# SCH_Tower_Panda_Hat_2023-01-18.net
KiCad netlist of a schematic drawn in EasyEDA
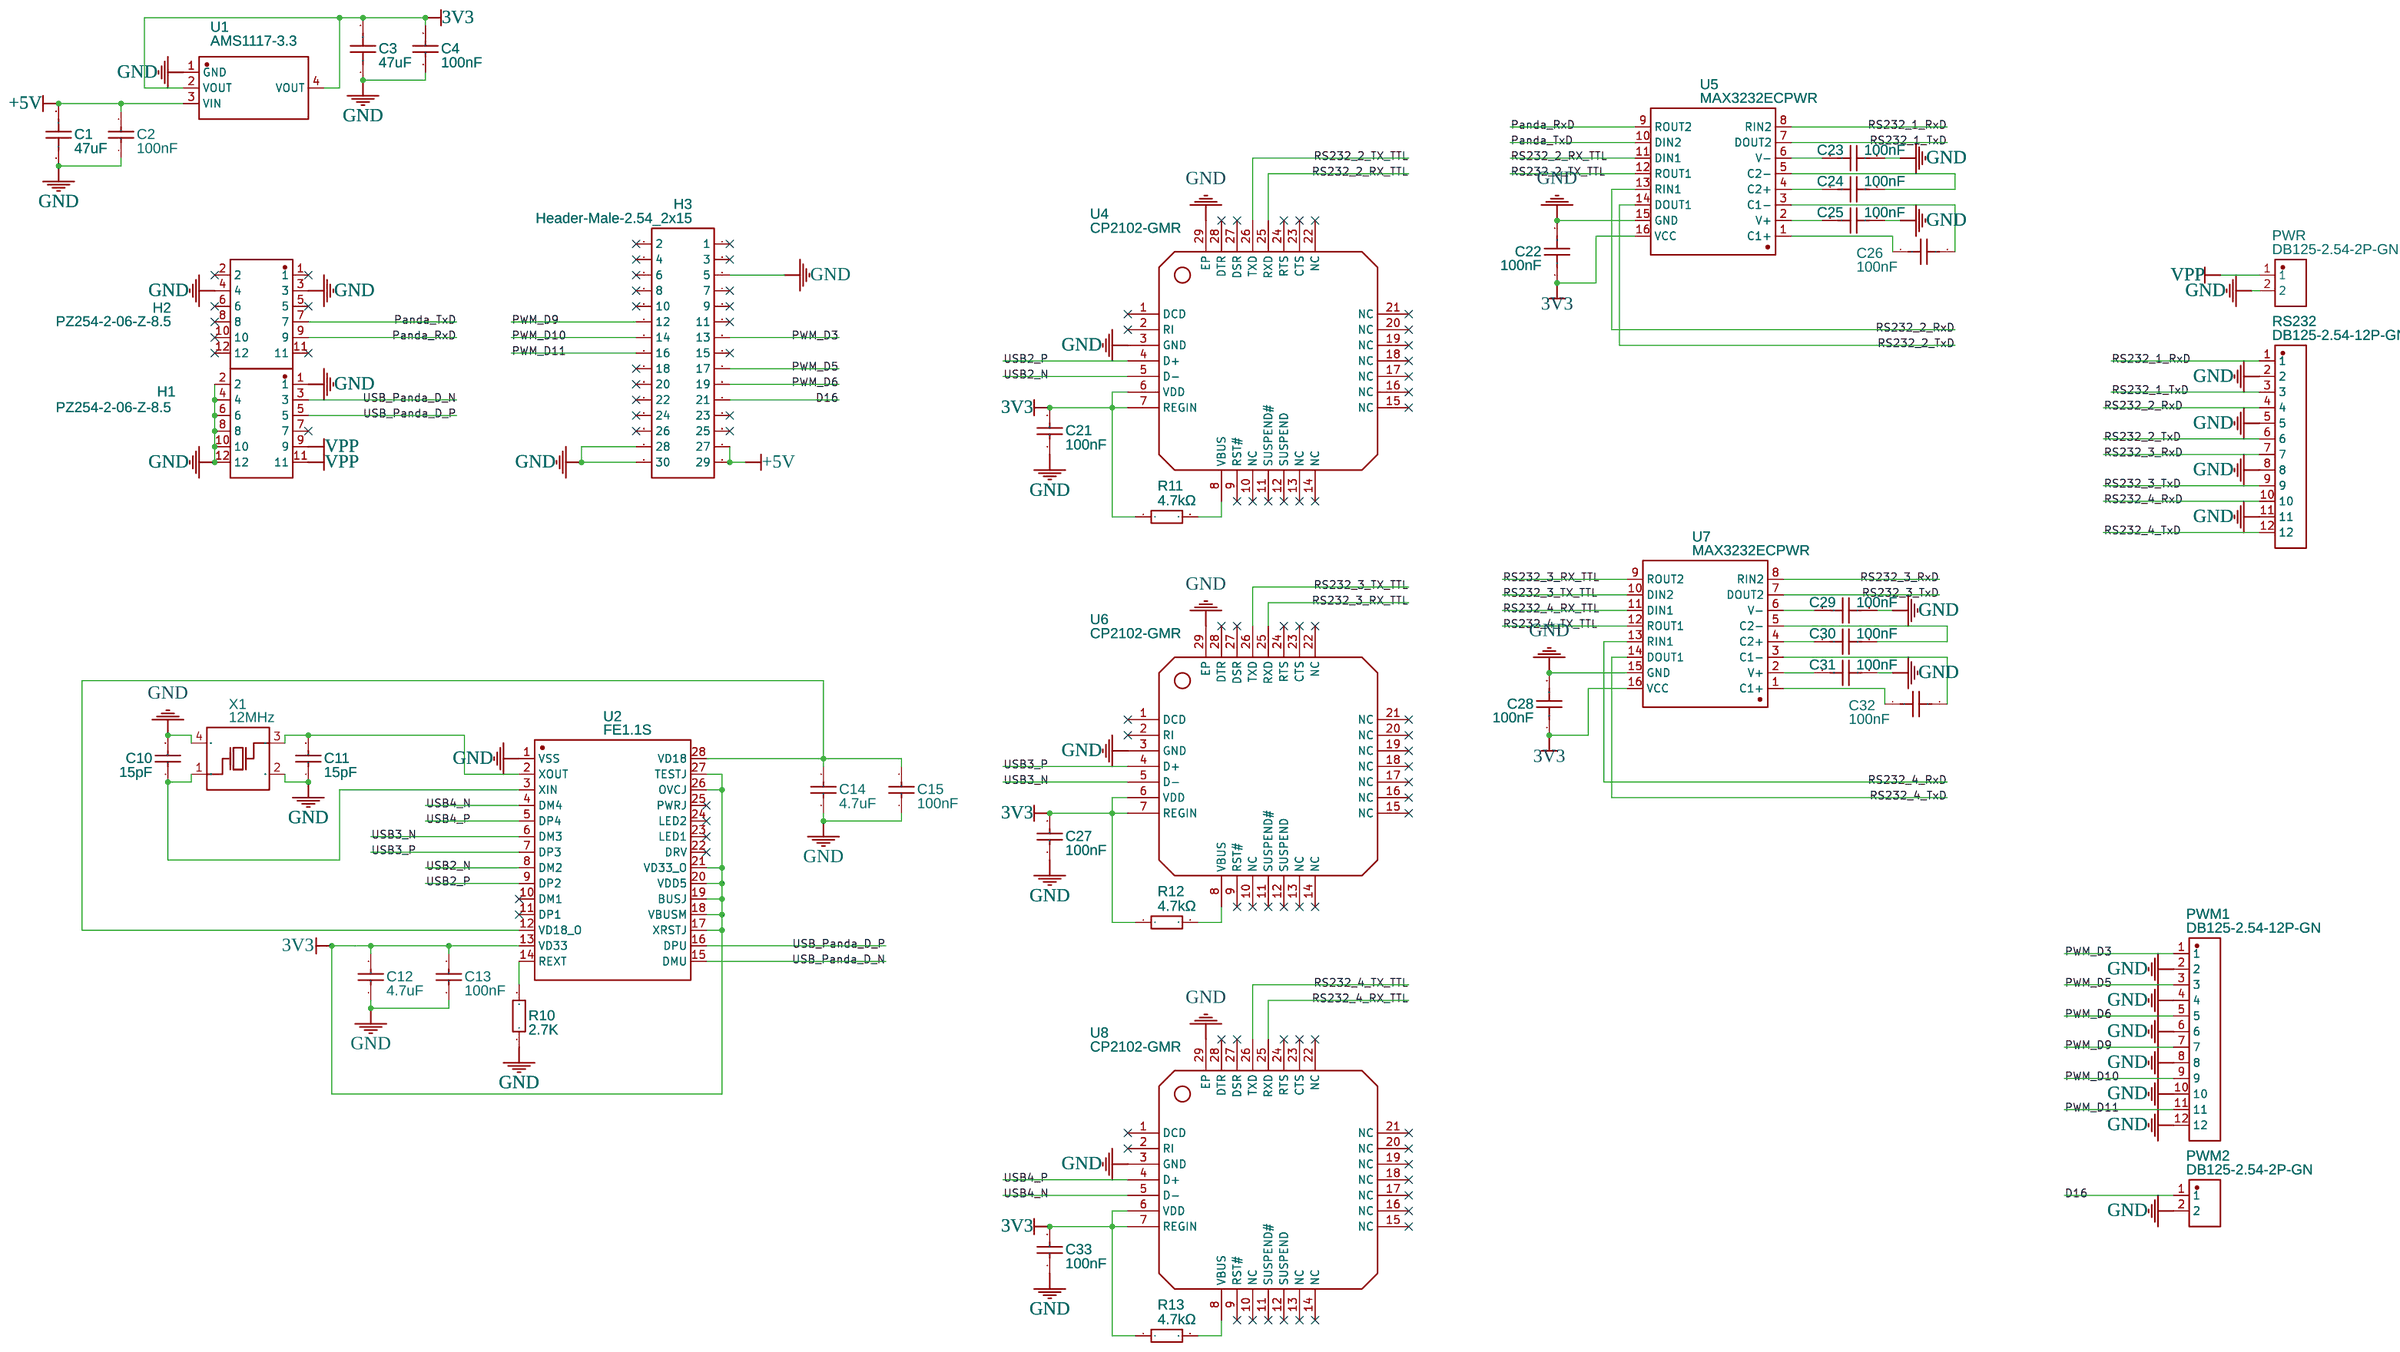
[diagram p0: schematic sheet]

(export (version "E")
  (design (tool "Eeschema 10.0.6"))
  (components
    (comp (ref "C1")
      (value "47uF")
      (fields
        (field (name "BOM_Manufacturer Part") "CL31A476MPHNNNE")
        (field (name "BOM_Supplier Part") "C96123")
      )
      (libsource (lib "") (part "CL31A476MPHNNNE"))
    )
    (comp (ref "C2")
      (value "100nF")
      (fields
        (field (name "BOM_Manufacturer Part") "CL05B104KO5NNNC")
        (field (name "BOM_Supplier Part") "C1525")
      )
      (libsource (lib "") (part "CL05B104KO5NNNC"))
    )
    (comp (ref "C3")
      (value "47uF")
      (fields
        (field (name "BOM_Manufacturer Part") "CL31A476MPHNNNE")
        (field (name "BOM_Supplier Part") "C96123")
      )
      (libsource (lib "") (part "CL31A476MPHNNNE"))
    )
    (comp (ref "C4")
      (value "100nF")
      (fields
        (field (name "BOM_Manufacturer Part") "CL05B104KO5NNNC")
        (field (name "BOM_Supplier Part") "C1525")
      )
      (libsource (lib "") (part "CL05B104KO5NNNC"))
    )
    (comp (ref "C10")
      (value "15pF")
      (fields
        (field (name "BOM_Manufacturer Part") "0402CG150J500NT")
        (field (name "BOM_Supplier Part") "C1548")
      )
      (libsource (lib "") (part "0402CG150J500NT_1"))
    )
    (comp (ref "C11")
      (value "15pF")
      (fields
        (field (name "BOM_Manufacturer Part") "0402CG150J500NT")
        (field (name "BOM_Supplier Part") "C1548")
      )
      (libsource (lib "") (part "0402CG150J500NT"))
    )
    (comp (ref "C12")
      (value "4.7uF")
      (fields
        (field (name "BOM_Manufacturer Part") "CL05A475MP5NRNC")
        (field (name "BOM_Supplier Part") "C23733")
      )
      (libsource (lib "") (part "CL05A475MP5NRNC"))
    )
    (comp (ref "C13")
      (value "100nF")
      (fields
        (field (name "BOM_Manufacturer Part") "CL05B104KO5NNNC")
        (field (name "BOM_Supplier Part") "C1525")
      )
      (libsource (lib "") (part "CL05B104KO5NNNC"))
    )
    (comp (ref "C14")
      (value "4.7uF")
      (fields
        (field (name "BOM_Manufacturer Part") "CL05A475MP5NRNC")
        (field (name "BOM_Supplier Part") "C23733")
      )
      (libsource (lib "") (part "CL05A475MP5NRNC"))
    )
    (comp (ref "C15")
      (value "100nF")
      (fields
        (field (name "BOM_Manufacturer Part") "CL05B104KO5NNNC")
        (field (name "BOM_Supplier Part") "C1525")
      )
      (libsource (lib "") (part "CL05B104KO5NNNC"))
    )
    (comp (ref "C21")
      (value "100nF")
      (fields
        (field (name "BOM_Manufacturer Part") "CL05B104KO5NNNC")
        (field (name "BOM_Supplier Part") "C1525")
      )
      (libsource (lib "") (part "CL05B104KO5NNNC"))
    )
    (comp (ref "C22")
      (value "100nF")
      (fields
        (field (name "BOM_Manufacturer Part") "CL05B104KB54PNC")
        (field (name "BOM_Supplier Part") "C307331")
      )
      (libsource (lib "") (part "CL05B104KB54PNC_1"))
    )
    (comp (ref "C23")
      (value "100nF")
      (fields
        (field (name "BOM_Manufacturer Part") "CL05B104KB54PNC")
        (field (name "BOM_Supplier Part") "C307331")
      )
      (libsource (lib "") (part "CL05B104KB54PNC"))
    )
    (comp (ref "C24")
      (value "100nF")
      (fields
        (field (name "BOM_Manufacturer Part") "CL05B104KB54PNC")
        (field (name "BOM_Supplier Part") "C307331")
      )
      (libsource (lib "") (part "CL05B104KB54PNC"))
    )
    (comp (ref "C25")
      (value "100nF")
      (fields
        (field (name "BOM_Manufacturer Part") "CL05B104KB54PNC")
        (field (name "BOM_Supplier Part") "C307331")
      )
      (libsource (lib "") (part "CL05B104KB54PNC"))
    )
    (comp (ref "C26")
      (value "100nF")
      (fields
        (field (name "BOM_Manufacturer Part") "CL05B104KB54PNC")
        (field (name "BOM_Supplier Part") "C307331")
      )
      (libsource (lib "") (part "CL05B104KB54PNC"))
    )
    (comp (ref "C27")
      (value "100nF")
      (fields
        (field (name "BOM_Manufacturer Part") "CL05B104KO5NNNC")
        (field (name "BOM_Supplier Part") "C1525")
      )
      (libsource (lib "") (part "CL05B104KO5NNNC"))
    )
    (comp (ref "C28")
      (value "100nF")
      (fields
        (field (name "BOM_Manufacturer Part") "CL05B104KB54PNC")
        (field (name "BOM_Supplier Part") "C307331")
      )
      (libsource (lib "") (part "CL05B104KB54PNC_1"))
    )
    (comp (ref "C29")
      (value "100nF")
      (fields
        (field (name "BOM_Manufacturer Part") "CL05B104KB54PNC")
        (field (name "BOM_Supplier Part") "C307331")
      )
      (libsource (lib "") (part "CL05B104KB54PNC"))
    )
    (comp (ref "C30")
      (value "100nF")
      (fields
        (field (name "BOM_Manufacturer Part") "CL05B104KB54PNC")
        (field (name "BOM_Supplier Part") "C307331")
      )
      (libsource (lib "") (part "CL05B104KB54PNC"))
    )
    (comp (ref "C31")
      (value "100nF")
      (fields
        (field (name "BOM_Manufacturer Part") "CL05B104KB54PNC")
        (field (name "BOM_Supplier Part") "C307331")
      )
      (libsource (lib "") (part "CL05B104KB54PNC"))
    )
    (comp (ref "C32")
      (value "100nF")
      (fields
        (field (name "BOM_Manufacturer Part") "CL05B104KB54PNC")
        (field (name "BOM_Supplier Part") "C307331")
      )
      (libsource (lib "") (part "CL05B104KB54PNC"))
    )
    (comp (ref "C33")
      (value "100nF")
      (fields
        (field (name "BOM_Manufacturer Part") "CL05B104KO5NNNC")
        (field (name "BOM_Supplier Part") "C1525")
      )
      (libsource (lib "") (part "CL05B104KO5NNNC"))
    )
    (comp (ref "H1")
      (value "PZ254-2-06-Z-8.5")
      (fields (field (name "BOM_Supplier Part") "C2894967"))
      (libsource (lib "") (part "PZ254-2-06-Z-8.5"))
    )
    (comp (ref "H2")
      (value "PZ254-2-06-Z-8.5")
      (fields (field (name "BOM_Supplier Part") "C2894967"))
      (libsource (lib "") (part "PZ254-2-06-Z-8.5"))
    )
    (comp (ref "H3")
      (value "Header-Male-2.54_2x15")
      (fields
        (field (name "BOM_Manufacturer Part") "2.54-2*15P双排针")
        (field (name "BOM_Supplier Part") "C56496")
      )
      (libsource (lib "") (part "Header-Male-2.54_2x15"))
    )
    (comp (ref "PWM1")
      (value "DB125-2.54-12P-GN")
      (fields
        (field (name "BOM_Manufacturer Part") "DB125-2.54-12P-GN-S")
        (field (name "BOM_Supplier Part") "C918129")
      )
      (libsource (lib "") (part "DB125-2.54-12P-GN_1"))
    )
    (comp (ref "PWM2")
      (value "DB125-2.54-2P-GN")
      (fields (field (name "BOM_Supplier Part") "C918120"))
      (libsource (lib "") (part "DB125-2.54-2P-GN_1"))
    )
    (comp (ref "PWR")
      (value "DB125-2.54-2P-GN")
      (fields (field (name "BOM_Supplier Part") "C918120"))
      (libsource (lib "") (part "DB125-2.54-2P-GN"))
    )
    (comp (ref "R10")
      (value "2.7K")
      (fields
        (field (name "BOM_Manufacturer Part") "0603WAF2701T5E")
        (field (name "BOM_Supplier Part") "C13167")
      )
      (libsource (lib "") (part "0603WAF2701T5E"))
    )
    (comp (ref "R11")
      (value "4.7kΩ")
      (fields
        (field (name "BOM_Manufacturer Part") "0402WGF4701TCE")
        (field (name "BOM_Supplier Part") "C25900")
      )
      (libsource (lib "") (part "0402WGF4701TCE"))
    )
    (comp (ref "R12")
      (value "4.7kΩ")
      (fields
        (field (name "BOM_Manufacturer Part") "0402WGF4701TCE")
        (field (name "BOM_Supplier Part") "C25900")
      )
      (libsource (lib "") (part "0402WGF4701TCE"))
    )
    (comp (ref "R13")
      (value "4.7kΩ")
      (fields
        (field (name "BOM_Manufacturer Part") "0402WGF4701TCE")
        (field (name "BOM_Supplier Part") "C25900")
      )
      (libsource (lib "") (part "0402WGF4701TCE"))
    )
    (comp (ref "RS232")
      (value "DB125-2.54-12P-GN")
      (fields
        (field (name "BOM_Manufacturer Part") "DB125-2.54-12P-GN-S")
        (field (name "BOM_Supplier Part") "C918129")
      )
      (libsource (lib "") (part "DB125-2.54-12P-GN"))
    )
    (comp (ref "U1")
      (value "AMS1117-3.3")
      (fields (field (name "BOM_Supplier Part") "C6186"))
      (libsource (lib "") (part "AMS1117-3.3"))
    )
    (comp (ref "U2")
      (value "FE1.1S")
      (fields (field (name "BOM_Supplier Part") "C9359"))
      (libsource (lib "") (part "FE1.1S"))
    )
    (comp (ref "U4")
      (value "CP2102-GMR")
      (fields (field (name "BOM_Supplier Part") "C6568"))
      (libsource (lib "") (part "CP2102-GMR"))
    )
    (comp (ref "U5")
      (value "MAX3232ECPWR")
      (fields (field (name "BOM_Supplier Part") "C11317"))
      (libsource (lib "") (part "MAX3232ECPWR"))
    )
    (comp (ref "U6")
      (value "CP2102-GMR")
      (fields (field (name "BOM_Supplier Part") "C6568"))
      (libsource (lib "") (part "CP2102-GMR"))
    )
    (comp (ref "U7")
      (value "MAX3232ECPWR")
      (fields (field (name "BOM_Supplier Part") "C11317"))
      (libsource (lib "") (part "MAX3232ECPWR"))
    )
    (comp (ref "U8")
      (value "CP2102-GMR")
      (fields (field (name "BOM_Supplier Part") "C6568"))
      (libsource (lib "") (part "CP2102-GMR"))
    )
    (comp (ref "X1")
      (value "12MHz")
      (fields
        (field (name "BOM_Manufacturer Part") "X322512MSB4SI")
        (field (name "BOM_Supplier Part") "C9002")
      )
      (libsource (lib "") (part "X322512MSB4SI"))
    )
  )
  (nets
    (net (code "1") (name "+5V") (class "Default")
      (node (ref "C1") (pin "2") (pinfunction "2_2") (pintype "unspecified"))
      (node (ref "C2") (pin "2") (pinfunction "2_2") (pintype "input"))
      (node (ref "H3") (pin "27") (pinfunction "27_27") (pintype "input"))
      (node (ref "H3") (pin "29") (pinfunction "29_29") (pintype "input"))
      (node (ref "U1") (pin "3") (pinfunction "VIN_3") (pintype "unspecified"))
    )
    (net (code "2") (name "/D16") (class "Default")
      (node (ref "H3") (pin "21") (pinfunction "21_21") (pintype "input"))
      (node (ref "PWM2") (pin "1") (pinfunction "1_1") (pintype "unspecified"))
    )
    (net (code "3") (name "/PWM_D3") (class "Default")
      (node (ref "H3") (pin "13") (pinfunction "13_13") (pintype "input"))
      (node (ref "PWM1") (pin "1") (pinfunction "1_1") (pintype "unspecified"))
    )
    (net (code "4") (name "/PWM_D5") (class "Default")
      (node (ref "H3") (pin "17") (pinfunction "17_17") (pintype "input"))
      (node (ref "PWM1") (pin "3") (pinfunction "3_3") (pintype "unspecified"))
    )
    (net (code "5") (name "/PWM_D6") (class "Default")
      (node (ref "H3") (pin "19") (pinfunction "19_19") (pintype "input"))
      (node (ref "PWM1") (pin "5") (pinfunction "5_5") (pintype "unspecified"))
    )
    (net (code "6") (name "/PWM_D9") (class "Default")
      (node (ref "H3") (pin "12") (pinfunction "12_12") (pintype "input"))
      (node (ref "PWM1") (pin "7") (pinfunction "7_7") (pintype "unspecified"))
    )
    (net (code "7") (name "/PWM_D10") (class "Default")
      (node (ref "H3") (pin "14") (pinfunction "14_14") (pintype "input"))
      (node (ref "PWM1") (pin "9") (pinfunction "9_9") (pintype "unspecified"))
    )
    (net (code "8") (name "/PWM_D11") (class "Default")
      (node (ref "H3") (pin "16") (pinfunction "16_16") (pintype "input"))
      (node (ref "PWM1") (pin "11") (pinfunction "11_11") (pintype "unspecified"))
    )
    (net (code "9") (name "/Panda_RxD") (class "Default")
      (node (ref "H2") (pin "9") (pinfunction "9_9") (pintype "unspecified"))
      (node (ref "U5") (pin "9") (pinfunction "ROUT2_9") (pintype "unspecified"))
    )
    (net (code "10") (name "/Panda_TxD") (class "Default")
      (node (ref "H2") (pin "7") (pinfunction "7_7") (pintype "unspecified"))
      (node (ref "U5") (pin "10") (pinfunction "DIN2_10") (pintype "unspecified"))
    )
    (net (code "11") (name "/RS232_1_RxD") (class "Default")
      (node (ref "RS232") (pin "1") (pinfunction "1_1") (pintype "unspecified"))
      (node (ref "U5") (pin "8") (pinfunction "RIN2_8") (pintype "unspecified"))
    )
    (net (code "12") (name "/RS232_1_TxD") (class "Default")
      (node (ref "RS232") (pin "3") (pinfunction "3_3") (pintype "unspecified"))
      (node (ref "U5") (pin "7") (pinfunction "DOUT2_7") (pintype "unspecified"))
    )
    (net (code "13") (name "/RS232_2_RX_TTL") (class "Default")
      (node (ref "U4") (pin "25") (pinfunction "RXD_25") (pintype "unspecified"))
      (node (ref "U5") (pin "11") (pinfunction "DIN1_11") (pintype "unspecified"))
    )
    (net (code "14") (name "/RS232_2_RxD") (class "Default")
      (node (ref "RS232") (pin "4") (pinfunction "4_4") (pintype "unspecified"))
      (node (ref "U5") (pin "13") (pinfunction "RIN1_13") (pintype "unspecified"))
    )
    (net (code "15") (name "/RS232_2_TX_TTL") (class "Default")
      (node (ref "U4") (pin "26") (pinfunction "TXD_26") (pintype "unspecified"))
      (node (ref "U5") (pin "12") (pinfunction "ROUT1_12") (pintype "unspecified"))
    )
    (net (code "16") (name "/RS232_2_TxD") (class "Default")
      (node (ref "RS232") (pin "6") (pinfunction "6_6") (pintype "unspecified"))
      (node (ref "U5") (pin "14") (pinfunction "DOUT1_14") (pintype "unspecified"))
    )
    (net (code "17") (name "/RS232_3_RX_TTL") (class "Default")
      (node (ref "U6") (pin "25") (pinfunction "RXD_25") (pintype "unspecified"))
      (node (ref "U7") (pin "9") (pinfunction "ROUT2_9") (pintype "unspecified"))
    )
    (net (code "18") (name "/RS232_3_RxD") (class "Default")
      (node (ref "RS232") (pin "7") (pinfunction "7_7") (pintype "unspecified"))
      (node (ref "U7") (pin "8") (pinfunction "RIN2_8") (pintype "unspecified"))
    )
    (net (code "19") (name "/RS232_3_TX_TTL") (class "Default")
      (node (ref "U6") (pin "26") (pinfunction "TXD_26") (pintype "unspecified"))
      (node (ref "U7") (pin "10") (pinfunction "DIN2_10") (pintype "unspecified"))
    )
    (net (code "20") (name "/RS232_3_TxD") (class "Default")
      (node (ref "RS232") (pin "9") (pinfunction "9_9") (pintype "unspecified"))
      (node (ref "U7") (pin "7") (pinfunction "DOUT2_7") (pintype "unspecified"))
    )
    (net (code "21") (name "/RS232_4_RX_TTL") (class "Default")
      (node (ref "U7") (pin "11") (pinfunction "DIN1_11") (pintype "unspecified"))
      (node (ref "U8") (pin "25") (pinfunction "RXD_25") (pintype "unspecified"))
    )
    (net (code "22") (name "/RS232_4_RxD") (class "Default")
      (node (ref "RS232") (pin "10") (pinfunction "10_10") (pintype "unspecified"))
      (node (ref "U7") (pin "13") (pinfunction "RIN1_13") (pintype "unspecified"))
    )
    (net (code "23") (name "/RS232_4_TX_TTL") (class "Default")
      (node (ref "U7") (pin "12") (pinfunction "ROUT1_12") (pintype "unspecified"))
      (node (ref "U8") (pin "26") (pinfunction "TXD_26") (pintype "unspecified"))
    )
    (net (code "24") (name "/RS232_4_TxD") (class "Default")
      (node (ref "RS232") (pin "12") (pinfunction "12_12") (pintype "unspecified"))
      (node (ref "U7") (pin "14") (pinfunction "DOUT1_14") (pintype "unspecified"))
    )
    (net (code "25") (name "/USB2_N") (class "Default")
      (node (ref "U2") (pin "8") (pinfunction "DM2_8") (pintype "unspecified"))
      (node (ref "U4") (pin "5") (pinfunction "D-_5") (pintype "unspecified"))
    )
    (net (code "26") (name "/USB2_P") (class "Default")
      (node (ref "U2") (pin "9") (pinfunction "DP2_9") (pintype "unspecified"))
      (node (ref "U4") (pin "4") (pinfunction "D+_4") (pintype "unspecified"))
    )
    (net (code "27") (name "/USB3_N") (class "Default")
      (node (ref "U2") (pin "6") (pinfunction "DM3_6") (pintype "unspecified"))
      (node (ref "U6") (pin "5") (pinfunction "D-_5") (pintype "unspecified"))
    )
    (net (code "28") (name "/USB3_P") (class "Default")
      (node (ref "U2") (pin "7") (pinfunction "DP3_7") (pintype "unspecified"))
      (node (ref "U6") (pin "4") (pinfunction "D+_4") (pintype "unspecified"))
    )
    (net (code "29") (name "/USB4_N") (class "Default")
      (node (ref "U2") (pin "4") (pinfunction "DM4_4") (pintype "unspecified"))
      (node (ref "U8") (pin "5") (pinfunction "D-_5") (pintype "unspecified"))
    )
    (net (code "30") (name "/USB4_P") (class "Default")
      (node (ref "U2") (pin "5") (pinfunction "DP4_5") (pintype "unspecified"))
      (node (ref "U8") (pin "4") (pinfunction "D+_4") (pintype "unspecified"))
    )
    (net (code "31") (name "/USB_Panda_D_N") (class "Default")
      (node (ref "H1") (pin "3") (pinfunction "3_3") (pintype "unspecified"))
      (node (ref "U2") (pin "15") (pinfunction "DMU_15") (pintype "unspecified"))
    )
    (net (code "32") (name "/USB_Panda_D_P") (class "Default")
      (node (ref "H1") (pin "5") (pinfunction "5_5") (pintype "unspecified"))
      (node (ref "U2") (pin "16") (pinfunction "DPU_16") (pintype "unspecified"))
    )
    (net (code "33") (name "3V3") (class "Default")
      (node (ref "C12") (pin "2") (pinfunction "2_2") (pintype "input"))
      (node (ref "C13") (pin "2") (pinfunction "2_2") (pintype "input"))
      (node (ref "C21") (pin "2") (pinfunction "2_2") (pintype "input"))
      (node (ref "C22") (pin "1") (pinfunction "1_1") (pintype "unspecified"))
      (node (ref "C27") (pin "2") (pinfunction "2_2") (pintype "input"))
      (node (ref "C28") (pin "1") (pinfunction "1_1") (pintype "unspecified"))
      (node (ref "C3") (pin "2") (pinfunction "2_2") (pintype "unspecified"))
      (node (ref "C33") (pin "2") (pinfunction "2_2") (pintype "input"))
      (node (ref "C4") (pin "2") (pinfunction "2_2") (pintype "input"))
      (node (ref "R11") (pin "1") (pinfunction "1_1") (pintype "input"))
      (node (ref "R12") (pin "1") (pinfunction "1_1") (pintype "input"))
      (node (ref "R13") (pin "1") (pinfunction "1_1") (pintype "input"))
      (node (ref "U1") (pin "2") (pinfunction "VOUT_2") (pintype "unspecified"))
      (node (ref "U1") (pin "4") (pinfunction "VOUT_4") (pintype "unspecified"))
      (node (ref "U2") (pin "13") (pinfunction "VD33_13") (pintype "unspecified"))
      (node (ref "U2") (pin "17") (pinfunction "XRSTJ_17") (pintype "unspecified"))
      (node (ref "U2") (pin "18") (pinfunction "VBUSM_18") (pintype "unspecified"))
      (node (ref "U2") (pin "19") (pinfunction "BUSJ_19") (pintype "unspecified"))
      (node (ref "U2") (pin "20") (pinfunction "VDD5_20") (pintype "unspecified"))
      (node (ref "U2") (pin "21") (pinfunction "VD33_O_21") (pintype "unspecified"))
      (node (ref "U2") (pin "26") (pinfunction "OVCJ_26") (pintype "unspecified"))
      (node (ref "U2") (pin "27") (pinfunction "TESTJ_27") (pintype "unspecified"))
      (node (ref "U4") (pin "6") (pinfunction "VDD_6") (pintype "unspecified"))
      (node (ref "U4") (pin "7") (pinfunction "REGIN_7") (pintype "unspecified"))
      (node (ref "U5") (pin "16") (pinfunction "VCC_16") (pintype "unspecified"))
      (node (ref "U6") (pin "6") (pinfunction "VDD_6") (pintype "unspecified"))
      (node (ref "U6") (pin "7") (pinfunction "REGIN_7") (pintype "unspecified"))
      (node (ref "U7") (pin "16") (pinfunction "VCC_16") (pintype "unspecified"))
      (node (ref "U8") (pin "6") (pinfunction "VDD_6") (pintype "unspecified"))
      (node (ref "U8") (pin "7") (pinfunction "REGIN_7") (pintype "unspecified"))
    )
    (net (code "34") (name "GND") (class "Default")
      (node (ref "C1") (pin "1") (pinfunction "1_1") (pintype "unspecified"))
      (node (ref "C10") (pin "2") (pinfunction "2_2") (pintype "input"))
      (node (ref "C11") (pin "1") (pinfunction "1_1") (pintype "input"))
      (node (ref "C12") (pin "1") (pinfunction "1_1") (pintype "input"))
      (node (ref "C13") (pin "1") (pinfunction "1_1") (pintype "input"))
      (node (ref "C14") (pin "1") (pinfunction "1_1") (pintype "input"))
      (node (ref "C15") (pin "1") (pinfunction "1_1") (pintype "input"))
      (node (ref "C2") (pin "1") (pinfunction "1_1") (pintype "input"))
      (node (ref "C21") (pin "1") (pinfunction "1_1") (pintype "input"))
      (node (ref "C22") (pin "2") (pinfunction "2_2") (pintype "unspecified"))
      (node (ref "C23") (pin "2") (pinfunction "2_2") (pintype "unspecified"))
      (node (ref "C25") (pin "2") (pinfunction "2_2") (pintype "unspecified"))
      (node (ref "C27") (pin "1") (pinfunction "1_1") (pintype "input"))
      (node (ref "C28") (pin "2") (pinfunction "2_2") (pintype "unspecified"))
      (node (ref "C29") (pin "2") (pinfunction "2_2") (pintype "unspecified"))
      (node (ref "C3") (pin "1") (pinfunction "1_1") (pintype "unspecified"))
      (node (ref "C31") (pin "2") (pinfunction "2_2") (pintype "unspecified"))
      (node (ref "C33") (pin "1") (pinfunction "1_1") (pintype "input"))
      (node (ref "C4") (pin "1") (pinfunction "1_1") (pintype "input"))
      (node (ref "H1") (pin "1") (pinfunction "1_1") (pintype "unspecified"))
      (node (ref "H1") (pin "10") (pinfunction "10_10") (pintype "unspecified"))
      (node (ref "H1") (pin "12") (pinfunction "12_12") (pintype "unspecified"))
      (node (ref "H1") (pin "2") (pinfunction "2_2") (pintype "unspecified"))
      (node (ref "H1") (pin "4") (pinfunction "4_4") (pintype "unspecified"))
      (node (ref "H1") (pin "6") (pinfunction "6_6") (pintype "unspecified"))
      (node (ref "H1") (pin "8") (pinfunction "8_8") (pintype "unspecified"))
      (node (ref "H2") (pin "3") (pinfunction "3_3") (pintype "unspecified"))
      (node (ref "H2") (pin "4") (pinfunction "4_4") (pintype "unspecified"))
      (node (ref "H3") (pin "28") (pinfunction "28_28") (pintype "input"))
      (node (ref "H3") (pin "30") (pinfunction "30_30") (pintype "input"))
      (node (ref "H3") (pin "5") (pinfunction "5_5") (pintype "input"))
      (node (ref "PWM1") (pin "10") (pinfunction "10_10") (pintype "unspecified"))
      (node (ref "PWM1") (pin "12") (pinfunction "12_12") (pintype "unspecified"))
      (node (ref "PWM1") (pin "2") (pinfunction "2_2") (pintype "unspecified"))
      (node (ref "PWM1") (pin "4") (pinfunction "4_4") (pintype "unspecified"))
      (node (ref "PWM1") (pin "6") (pinfunction "6_6") (pintype "unspecified"))
      (node (ref "PWM1") (pin "8") (pinfunction "8_8") (pintype "unspecified"))
      (node (ref "PWM2") (pin "2") (pinfunction "2_2") (pintype "unspecified"))
      (node (ref "PWR") (pin "2") (pinfunction "2_2") (pintype "unspecified"))
      (node (ref "R10") (pin "1") (pinfunction "1_1") (pintype "input"))
      (node (ref "RS232") (pin "11") (pinfunction "11_11") (pintype "unspecified"))
      (node (ref "RS232") (pin "2") (pinfunction "2_2") (pintype "unspecified"))
      (node (ref "RS232") (pin "5") (pinfunction "5_5") (pintype "unspecified"))
      (node (ref "RS232") (pin "8") (pinfunction "8_8") (pintype "unspecified"))
      (node (ref "U1") (pin "1") (pinfunction "GND_1") (pintype "unspecified"))
      (node (ref "U2") (pin "1") (pinfunction "VSS_1") (pintype "unspecified"))
      (node (ref "U4") (pin "29") (pinfunction "EP_29") (pintype "unspecified"))
      (node (ref "U4") (pin "3") (pinfunction "GND_3") (pintype "unspecified"))
      (node (ref "U5") (pin "15") (pinfunction "GND_15") (pintype "unspecified"))
      (node (ref "U6") (pin "29") (pinfunction "EP_29") (pintype "unspecified"))
      (node (ref "U6") (pin "3") (pinfunction "GND_3") (pintype "unspecified"))
      (node (ref "U7") (pin "15") (pinfunction "GND_15") (pintype "unspecified"))
      (node (ref "U8") (pin "29") (pinfunction "EP_29") (pintype "unspecified"))
      (node (ref "U8") (pin "3") (pinfunction "GND_3") (pintype "unspecified"))
      (node (ref "X1") (pin "2") (pinfunction "GND_2") (pintype "unspecified"))
      (node (ref "X1") (pin "4") (pinfunction "GND_4") (pintype "unspecified"))
    )
    (net (code "35") (name "Net-(U2-REXT)") (class "Default")
      (node (ref "R10") (pin "2") (pinfunction "2_2") (pintype "input"))
      (node (ref "U2") (pin "14") (pinfunction "REXT_14") (pintype "unspecified"))
    )
    (net (code "36") (name "Net-(U2-VD18)") (class "Default")
      (node (ref "C14") (pin "2") (pinfunction "2_2") (pintype "input"))
      (node (ref "C15") (pin "2") (pinfunction "2_2") (pintype "input"))
      (node (ref "U2") (pin "12") (pinfunction "VD18_O_12") (pintype "unspecified"))
      (node (ref "U2") (pin "28") (pinfunction "VD18_28") (pintype "unspecified"))
    )
    (net (code "37") (name "Net-(U2-XIN)") (class "Default")
      (node (ref "C10") (pin "1") (pinfunction "1_1") (pintype "input"))
      (node (ref "U2") (pin "3") (pinfunction "XIN_3") (pintype "unspecified"))
      (node (ref "X1") (pin "1") (pinfunction "OSC1_1") (pintype "unspecified"))
    )
    (net (code "38") (name "Net-(U2-XOUT)") (class "Default")
      (node (ref "C11") (pin "2") (pinfunction "2_2") (pintype "input"))
      (node (ref "U2") (pin "2") (pinfunction "XOUT_2") (pintype "unspecified"))
      (node (ref "X1") (pin "3") (pinfunction "OSC2_3") (pintype "unspecified"))
    )
    (net (code "39") (name "Net-(U4-VBUS)") (class "Default")
      (node (ref "R11") (pin "2") (pinfunction "2_2") (pintype "input"))
      (node (ref "U4") (pin "8") (pinfunction "VBUS_8") (pintype "unspecified"))
    )
    (net (code "40") (name "Net-(U5-C1+)") (class "Default")
      (node (ref "C26") (pin "1") (pinfunction "1_1") (pintype "unspecified"))
      (node (ref "U5") (pin "1") (pinfunction "C1+_1") (pintype "unspecified"))
    )
    (net (code "41") (name "Net-(U5-C1-)") (class "Default")
      (node (ref "C26") (pin "2") (pinfunction "2_2") (pintype "unspecified"))
      (node (ref "U5") (pin "3") (pinfunction "C1-_3") (pintype "unspecified"))
    )
    (net (code "42") (name "Net-(U5-C2+)") (class "Default")
      (node (ref "C24") (pin "1") (pinfunction "1_1") (pintype "unspecified"))
      (node (ref "U5") (pin "4") (pinfunction "C2+_4") (pintype "unspecified"))
    )
    (net (code "43") (name "Net-(U5-C2-)") (class "Default")
      (node (ref "C24") (pin "2") (pinfunction "2_2") (pintype "unspecified"))
      (node (ref "U5") (pin "5") (pinfunction "C2-_5") (pintype "unspecified"))
    )
    (net (code "44") (name "Net-(U5-V+)") (class "Default")
      (node (ref "C25") (pin "1") (pinfunction "1_1") (pintype "unspecified"))
      (node (ref "U5") (pin "2") (pinfunction "V+_2") (pintype "unspecified"))
    )
    (net (code "45") (name "Net-(U5-V-)") (class "Default")
      (node (ref "C23") (pin "1") (pinfunction "1_1") (pintype "unspecified"))
      (node (ref "U5") (pin "6") (pinfunction "V-_6") (pintype "unspecified"))
    )
    (net (code "46") (name "Net-(U6-VBUS)") (class "Default")
      (node (ref "R12") (pin "2") (pinfunction "2_2") (pintype "input"))
      (node (ref "U6") (pin "8") (pinfunction "VBUS_8") (pintype "unspecified"))
    )
    (net (code "47") (name "Net-(U7-C1+)") (class "Default")
      (node (ref "C32") (pin "1") (pinfunction "1_1") (pintype "unspecified"))
      (node (ref "U7") (pin "1") (pinfunction "C1+_1") (pintype "unspecified"))
    )
    (net (code "48") (name "Net-(U7-C1-)") (class "Default")
      (node (ref "C32") (pin "2") (pinfunction "2_2") (pintype "unspecified"))
      (node (ref "U7") (pin "3") (pinfunction "C1-_3") (pintype "unspecified"))
    )
    (net (code "49") (name "Net-(U7-C2+)") (class "Default")
      (node (ref "C30") (pin "1") (pinfunction "1_1") (pintype "unspecified"))
      (node (ref "U7") (pin "4") (pinfunction "C2+_4") (pintype "unspecified"))
    )
    (net (code "50") (name "Net-(U7-C2-)") (class "Default")
      (node (ref "C30") (pin "2") (pinfunction "2_2") (pintype "unspecified"))
      (node (ref "U7") (pin "5") (pinfunction "C2-_5") (pintype "unspecified"))
    )
    (net (code "51") (name "Net-(U7-V+)") (class "Default")
      (node (ref "C31") (pin "1") (pinfunction "1_1") (pintype "unspecified"))
      (node (ref "U7") (pin "2") (pinfunction "V+_2") (pintype "unspecified"))
    )
    (net (code "52") (name "Net-(U7-V-)") (class "Default")
      (node (ref "C29") (pin "1") (pinfunction "1_1") (pintype "unspecified"))
      (node (ref "U7") (pin "6") (pinfunction "V-_6") (pintype "unspecified"))
    )
    (net (code "53") (name "Net-(U8-VBUS)") (class "Default")
      (node (ref "R13") (pin "2") (pinfunction "2_2") (pintype "input"))
      (node (ref "U8") (pin "8") (pinfunction "VBUS_8") (pintype "unspecified"))
    )
    (net (code "54") (name "VPP") (class "Default")
      (node (ref "H1") (pin "11") (pinfunction "11_11") (pintype "unspecified"))
      (node (ref "H1") (pin "9") (pinfunction "9_9") (pintype "unspecified"))
      (node (ref "PWR") (pin "1") (pinfunction "1_1") (pintype "unspecified"))
    )
    (net (code "55") (name "unconnected-(H1-Pad7)") (class "Default")
      (node (ref "H1") (pin "7") (pinfunction "7_7") (pintype "unspecified+no_connect"))
    )
    (net (code "56") (name "unconnected-(H2-Pad1)") (class "Default")
      (node (ref "H2") (pin "1") (pinfunction "1_1") (pintype "unspecified+no_connect"))
    )
    (net (code "57") (name "unconnected-(H2-Pad2)") (class "Default")
      (node (ref "H2") (pin "2") (pinfunction "2_2") (pintype "unspecified+no_connect"))
    )
    (net (code "58") (name "unconnected-(H2-Pad5)") (class "Default")
      (node (ref "H2") (pin "5") (pinfunction "5_5") (pintype "unspecified+no_connect"))
    )
    (net (code "59") (name "unconnected-(H2-Pad6)") (class "Default")
      (node (ref "H2") (pin "6") (pinfunction "6_6") (pintype "unspecified+no_connect"))
    )
    (net (code "60") (name "unconnected-(H2-Pad8)") (class "Default")
      (node (ref "H2") (pin "8") (pinfunction "8_8") (pintype "unspecified+no_connect"))
    )
    (net (code "61") (name "unconnected-(H2-Pad10)") (class "Default")
      (node (ref "H2") (pin "10") (pinfunction "10_10") (pintype "unspecified+no_connect"))
    )
    (net (code "62") (name "unconnected-(H2-Pad11)") (class "Default")
      (node (ref "H2") (pin "11") (pinfunction "11_11") (pintype "unspecified+no_connect"))
    )
    (net (code "63") (name "unconnected-(H2-Pad12)") (class "Default")
      (node (ref "H2") (pin "12") (pinfunction "12_12") (pintype "unspecified+no_connect"))
    )
    (net (code "64") (name "unconnected-(H3-Pad1)") (class "Default")
      (node (ref "H3") (pin "1") (pinfunction "1_1") (pintype "input+no_connect"))
    )
    (net (code "65") (name "unconnected-(H3-Pad2)") (class "Default")
      (node (ref "H3") (pin "2") (pinfunction "2_2") (pintype "input+no_connect"))
    )
    (net (code "66") (name "unconnected-(H3-Pad3)") (class "Default")
      (node (ref "H3") (pin "3") (pinfunction "3_3") (pintype "input+no_connect"))
    )
    (net (code "67") (name "unconnected-(H3-Pad4)") (class "Default")
      (node (ref "H3") (pin "4") (pinfunction "4_4") (pintype "input+no_connect"))
    )
    (net (code "68") (name "unconnected-(H3-Pad6)") (class "Default")
      (node (ref "H3") (pin "6") (pinfunction "6_6") (pintype "input+no_connect"))
    )
    (net (code "69") (name "unconnected-(H3-Pad7)") (class "Default")
      (node (ref "H3") (pin "7") (pinfunction "7_7") (pintype "input+no_connect"))
    )
    (net (code "70") (name "unconnected-(H3-Pad8)") (class "Default")
      (node (ref "H3") (pin "8") (pinfunction "8_8") (pintype "input+no_connect"))
    )
    (net (code "71") (name "unconnected-(H3-Pad9)") (class "Default")
      (node (ref "H3") (pin "9") (pinfunction "9_9") (pintype "input+no_connect"))
    )
    (net (code "72") (name "unconnected-(H3-Pad10)") (class "Default")
      (node (ref "H3") (pin "10") (pinfunction "10_10") (pintype "input+no_connect"))
    )
    (net (code "73") (name "unconnected-(H3-Pad11)") (class "Default")
      (node (ref "H3") (pin "11") (pinfunction "11_11") (pintype "input+no_connect"))
    )
    (net (code "74") (name "unconnected-(H3-Pad15)") (class "Default")
      (node (ref "H3") (pin "15") (pinfunction "15_15") (pintype "input+no_connect"))
    )
    (net (code "75") (name "unconnected-(H3-Pad18)") (class "Default")
      (node (ref "H3") (pin "18") (pinfunction "18_18") (pintype "input+no_connect"))
    )
    (net (code "76") (name "unconnected-(H3-Pad20)") (class "Default")
      (node (ref "H3") (pin "20") (pinfunction "20_20") (pintype "input+no_connect"))
    )
    (net (code "77") (name "unconnected-(H3-Pad22)") (class "Default")
      (node (ref "H3") (pin "22") (pinfunction "22_22") (pintype "input+no_connect"))
    )
    (net (code "78") (name "unconnected-(H3-Pad23)") (class "Default")
      (node (ref "H3") (pin "23") (pinfunction "23_23") (pintype "input+no_connect"))
    )
    (net (code "79") (name "unconnected-(H3-Pad24)") (class "Default")
      (node (ref "H3") (pin "24") (pinfunction "24_24") (pintype "input+no_connect"))
    )
    (net (code "80") (name "unconnected-(H3-Pad25)") (class "Default")
      (node (ref "H3") (pin "25") (pinfunction "25_25") (pintype "input+no_connect"))
    )
    (net (code "81") (name "unconnected-(H3-Pad26)") (class "Default")
      (node (ref "H3") (pin "26") (pinfunction "26_26") (pintype "input+no_connect"))
    )
    (net (code "82") (name "unconnected-(U2-DM1-Pad10)") (class "Default")
      (node (ref "U2") (pin "10") (pinfunction "DM1_10") (pintype "unspecified+no_connect"))
    )
    (net (code "83") (name "unconnected-(U2-DP1-Pad11)") (class "Default")
      (node (ref "U2") (pin "11") (pinfunction "DP1_11") (pintype "unspecified+no_connect"))
    )
    (net (code "84") (name "unconnected-(U2-DRV-Pad22)") (class "Default")
      (node (ref "U2") (pin "22") (pinfunction "DRV_22") (pintype "unspecified+no_connect"))
    )
    (net (code "85") (name "unconnected-(U2-LED1-Pad23)") (class "Default")
      (node (ref "U2") (pin "23") (pinfunction "LED1_23") (pintype "unspecified+no_connect"))
    )
    (net (code "86") (name "unconnected-(U2-LED2-Pad24)") (class "Default")
      (node (ref "U2") (pin "24") (pinfunction "LED2_24") (pintype "unspecified+no_connect"))
    )
    (net (code "87") (name "unconnected-(U2-PWRJ-Pad25)") (class "Default")
      (node (ref "U2") (pin "25") (pinfunction "PWRJ_25") (pintype "unspecified+no_connect"))
    )
    (net (code "88") (name "unconnected-(U4-CTS-Pad23)") (class "Default")
      (node (ref "U4") (pin "23") (pinfunction "CTS_23") (pintype "unspecified+no_connect"))
    )
    (net (code "89") (name "unconnected-(U4-DCD-Pad1)") (class "Default")
      (node (ref "U4") (pin "1") (pinfunction "DCD_1") (pintype "unspecified+no_connect"))
    )
    (net (code "90") (name "unconnected-(U4-DSR-Pad27)") (class "Default")
      (node (ref "U4") (pin "27") (pinfunction "DSR_27") (pintype "unspecified+no_connect"))
    )
    (net (code "91") (name "unconnected-(U4-DTR-Pad28)") (class "Default")
      (node (ref "U4") (pin "28") (pinfunction "DTR_28") (pintype "unspecified+no_connect"))
    )
    (net (code "92") (name "unconnected-(U4-NC-Pad10)") (class "Default")
      (node (ref "U4") (pin "10") (pinfunction "NC_10") (pintype "unspecified+no_connect"))
    )
    (net (code "93") (name "unconnected-(U4-NC-Pad13)") (class "Default")
      (node (ref "U4") (pin "13") (pinfunction "NC_13") (pintype "unspecified+no_connect"))
    )
    (net (code "94") (name "unconnected-(U4-NC-Pad14)") (class "Default")
      (node (ref "U4") (pin "14") (pinfunction "NC_14") (pintype "unspecified+no_connect"))
    )
    (net (code "95") (name "unconnected-(U4-NC-Pad15)") (class "Default")
      (node (ref "U4") (pin "15") (pinfunction "NC_15") (pintype "unspecified+no_connect"))
    )
    (net (code "96") (name "unconnected-(U4-NC-Pad16)") (class "Default")
      (node (ref "U4") (pin "16") (pinfunction "NC_16") (pintype "unspecified+no_connect"))
    )
    (net (code "97") (name "unconnected-(U4-NC-Pad17)") (class "Default")
      (node (ref "U4") (pin "17") (pinfunction "NC_17") (pintype "unspecified+no_connect"))
    )
    (net (code "98") (name "unconnected-(U4-NC-Pad18)") (class "Default")
      (node (ref "U4") (pin "18") (pinfunction "NC_18") (pintype "unspecified+no_connect"))
    )
    (net (code "99") (name "unconnected-(U4-NC-Pad19)") (class "Default")
      (node (ref "U4") (pin "19") (pinfunction "NC_19") (pintype "unspecified+no_connect"))
    )
    (net (code "100") (name "unconnected-(U4-NC-Pad20)") (class "Default")
      (node (ref "U4") (pin "20") (pinfunction "NC_20") (pintype "unspecified+no_connect"))
    )
    (net (code "101") (name "unconnected-(U4-NC-Pad21)") (class "Default")
      (node (ref "U4") (pin "21") (pinfunction "NC_21") (pintype "unspecified+no_connect"))
    )
    (net (code "102") (name "unconnected-(U4-NC-Pad22)") (class "Default")
      (node (ref "U4") (pin "22") (pinfunction "NC_22") (pintype "unspecified+no_connect"))
    )
    (net (code "103") (name "unconnected-(U4-RI-Pad2)") (class "Default")
      (node (ref "U4") (pin "2") (pinfunction "RI_2") (pintype "unspecified+no_connect"))
    )
    (net (code "104") (name "unconnected-(U4-RST#-Pad9)") (class "Default")
      (node (ref "U4") (pin "9") (pinfunction "RST#_9") (pintype "unspecified+no_connect"))
    )
    (net (code "105") (name "unconnected-(U4-RTS-Pad24)") (class "Default")
      (node (ref "U4") (pin "24") (pinfunction "RTS_24") (pintype "unspecified+no_connect"))
    )
    (net (code "106") (name "unconnected-(U4-SUSPEND#-Pad11)") (class "Default")
      (node (ref "U4") (pin "11") (pinfunction "SUSPEND#_11") (pintype "unspecified+no_connect"))
    )
    (net (code "107") (name "unconnected-(U4-SUSPEND-Pad12)") (class "Default")
      (node (ref "U4") (pin "12") (pinfunction "SUSPEND_12") (pintype "unspecified+no_connect"))
    )
    (net (code "108") (name "unconnected-(U6-CTS-Pad23)") (class "Default")
      (node (ref "U6") (pin "23") (pinfunction "CTS_23") (pintype "unspecified+no_connect"))
    )
    (net (code "109") (name "unconnected-(U6-DCD-Pad1)") (class "Default")
      (node (ref "U6") (pin "1") (pinfunction "DCD_1") (pintype "unspecified+no_connect"))
    )
    (net (code "110") (name "unconnected-(U6-DSR-Pad27)") (class "Default")
      (node (ref "U6") (pin "27") (pinfunction "DSR_27") (pintype "unspecified+no_connect"))
    )
    (net (code "111") (name "unconnected-(U6-DTR-Pad28)") (class "Default")
      (node (ref "U6") (pin "28") (pinfunction "DTR_28") (pintype "unspecified+no_connect"))
    )
    (net (code "112") (name "unconnected-(U6-NC-Pad10)") (class "Default")
      (node (ref "U6") (pin "10") (pinfunction "NC_10") (pintype "unspecified+no_connect"))
    )
    (net (code "113") (name "unconnected-(U6-NC-Pad13)") (class "Default")
      (node (ref "U6") (pin "13") (pinfunction "NC_13") (pintype "unspecified+no_connect"))
    )
    (net (code "114") (name "unconnected-(U6-NC-Pad14)") (class "Default")
      (node (ref "U6") (pin "14") (pinfunction "NC_14") (pintype "unspecified+no_connect"))
    )
    (net (code "115") (name "unconnected-(U6-NC-Pad15)") (class "Default")
      (node (ref "U6") (pin "15") (pinfunction "NC_15") (pintype "unspecified+no_connect"))
    )
    (net (code "116") (name "unconnected-(U6-NC-Pad16)") (class "Default")
      (node (ref "U6") (pin "16") (pinfunction "NC_16") (pintype "unspecified+no_connect"))
    )
    (net (code "117") (name "unconnected-(U6-NC-Pad17)") (class "Default")
      (node (ref "U6") (pin "17") (pinfunction "NC_17") (pintype "unspecified+no_connect"))
    )
    (net (code "118") (name "unconnected-(U6-NC-Pad18)") (class "Default")
      (node (ref "U6") (pin "18") (pinfunction "NC_18") (pintype "unspecified+no_connect"))
    )
    (net (code "119") (name "unconnected-(U6-NC-Pad19)") (class "Default")
      (node (ref "U6") (pin "19") (pinfunction "NC_19") (pintype "unspecified+no_connect"))
    )
    (net (code "120") (name "unconnected-(U6-NC-Pad20)") (class "Default")
      (node (ref "U6") (pin "20") (pinfunction "NC_20") (pintype "unspecified+no_connect"))
    )
    (net (code "121") (name "unconnected-(U6-NC-Pad21)") (class "Default")
      (node (ref "U6") (pin "21") (pinfunction "NC_21") (pintype "unspecified+no_connect"))
    )
    (net (code "122") (name "unconnected-(U6-NC-Pad22)") (class "Default")
      (node (ref "U6") (pin "22") (pinfunction "NC_22") (pintype "unspecified+no_connect"))
    )
    (net (code "123") (name "unconnected-(U6-RI-Pad2)") (class "Default")
      (node (ref "U6") (pin "2") (pinfunction "RI_2") (pintype "unspecified+no_connect"))
    )
    (net (code "124") (name "unconnected-(U6-RST#-Pad9)") (class "Default")
      (node (ref "U6") (pin "9") (pinfunction "RST#_9") (pintype "unspecified+no_connect"))
    )
    (net (code "125") (name "unconnected-(U6-RTS-Pad24)") (class "Default")
      (node (ref "U6") (pin "24") (pinfunction "RTS_24") (pintype "unspecified+no_connect"))
    )
    (net (code "126") (name "unconnected-(U6-SUSPEND#-Pad11)") (class "Default")
      (node (ref "U6") (pin "11") (pinfunction "SUSPEND#_11") (pintype "unspecified+no_connect"))
    )
    (net (code "127") (name "unconnected-(U6-SUSPEND-Pad12)") (class "Default")
      (node (ref "U6") (pin "12") (pinfunction "SUSPEND_12") (pintype "unspecified+no_connect"))
    )
    (net (code "128") (name "unconnected-(U8-CTS-Pad23)") (class "Default")
      (node (ref "U8") (pin "23") (pinfunction "CTS_23") (pintype "unspecified+no_connect"))
    )
    (net (code "129") (name "unconnected-(U8-DCD-Pad1)") (class "Default")
      (node (ref "U8") (pin "1") (pinfunction "DCD_1") (pintype "unspecified+no_connect"))
    )
    (net (code "130") (name "unconnected-(U8-DSR-Pad27)") (class "Default")
      (node (ref "U8") (pin "27") (pinfunction "DSR_27") (pintype "unspecified+no_connect"))
    )
    (net (code "131") (name "unconnected-(U8-DTR-Pad28)") (class "Default")
      (node (ref "U8") (pin "28") (pinfunction "DTR_28") (pintype "unspecified+no_connect"))
    )
    (net (code "132") (name "unconnected-(U8-NC-Pad10)") (class "Default")
      (node (ref "U8") (pin "10") (pinfunction "NC_10") (pintype "unspecified+no_connect"))
    )
    (net (code "133") (name "unconnected-(U8-NC-Pad13)") (class "Default")
      (node (ref "U8") (pin "13") (pinfunction "NC_13") (pintype "unspecified+no_connect"))
    )
    (net (code "134") (name "unconnected-(U8-NC-Pad14)") (class "Default")
      (node (ref "U8") (pin "14") (pinfunction "NC_14") (pintype "unspecified+no_connect"))
    )
    (net (code "135") (name "unconnected-(U8-NC-Pad15)") (class "Default")
      (node (ref "U8") (pin "15") (pinfunction "NC_15") (pintype "unspecified+no_connect"))
    )
    (net (code "136") (name "unconnected-(U8-NC-Pad16)") (class "Default")
      (node (ref "U8") (pin "16") (pinfunction "NC_16") (pintype "unspecified+no_connect"))
    )
    (net (code "137") (name "unconnected-(U8-NC-Pad17)") (class "Default")
      (node (ref "U8") (pin "17") (pinfunction "NC_17") (pintype "unspecified+no_connect"))
    )
    (net (code "138") (name "unconnected-(U8-NC-Pad18)") (class "Default")
      (node (ref "U8") (pin "18") (pinfunction "NC_18") (pintype "unspecified+no_connect"))
    )
    (net (code "139") (name "unconnected-(U8-NC-Pad19)") (class "Default")
      (node (ref "U8") (pin "19") (pinfunction "NC_19") (pintype "unspecified+no_connect"))
    )
    (net (code "140") (name "unconnected-(U8-NC-Pad20)") (class "Default")
      (node (ref "U8") (pin "20") (pinfunction "NC_20") (pintype "unspecified+no_connect"))
    )
    (net (code "141") (name "unconnected-(U8-NC-Pad21)") (class "Default")
      (node (ref "U8") (pin "21") (pinfunction "NC_21") (pintype "unspecified+no_connect"))
    )
    (net (code "142") (name "unconnected-(U8-NC-Pad22)") (class "Default")
      (node (ref "U8") (pin "22") (pinfunction "NC_22") (pintype "unspecified+no_connect"))
    )
    (net (code "143") (name "unconnected-(U8-RI-Pad2)") (class "Default")
      (node (ref "U8") (pin "2") (pinfunction "RI_2") (pintype "unspecified+no_connect"))
    )
    (net (code "144") (name "unconnected-(U8-RST#-Pad9)") (class "Default")
      (node (ref "U8") (pin "9") (pinfunction "RST#_9") (pintype "unspecified+no_connect"))
    )
    (net (code "145") (name "unconnected-(U8-RTS-Pad24)") (class "Default")
      (node (ref "U8") (pin "24") (pinfunction "RTS_24") (pintype "unspecified+no_connect"))
    )
    (net (code "146") (name "unconnected-(U8-SUSPEND#-Pad11)") (class "Default")
      (node (ref "U8") (pin "11") (pinfunction "SUSPEND#_11") (pintype "unspecified+no_connect"))
    )
    (net (code "147") (name "unconnected-(U8-SUSPEND-Pad12)") (class "Default")
      (node (ref "U8") (pin "12") (pinfunction "SUSPEND_12") (pintype "unspecified+no_connect"))
    )
  )
)
